# HIVE_SIGHT_DECAWAVE_B.net
KiCad netlist of a schematic drawn in Altium Designer
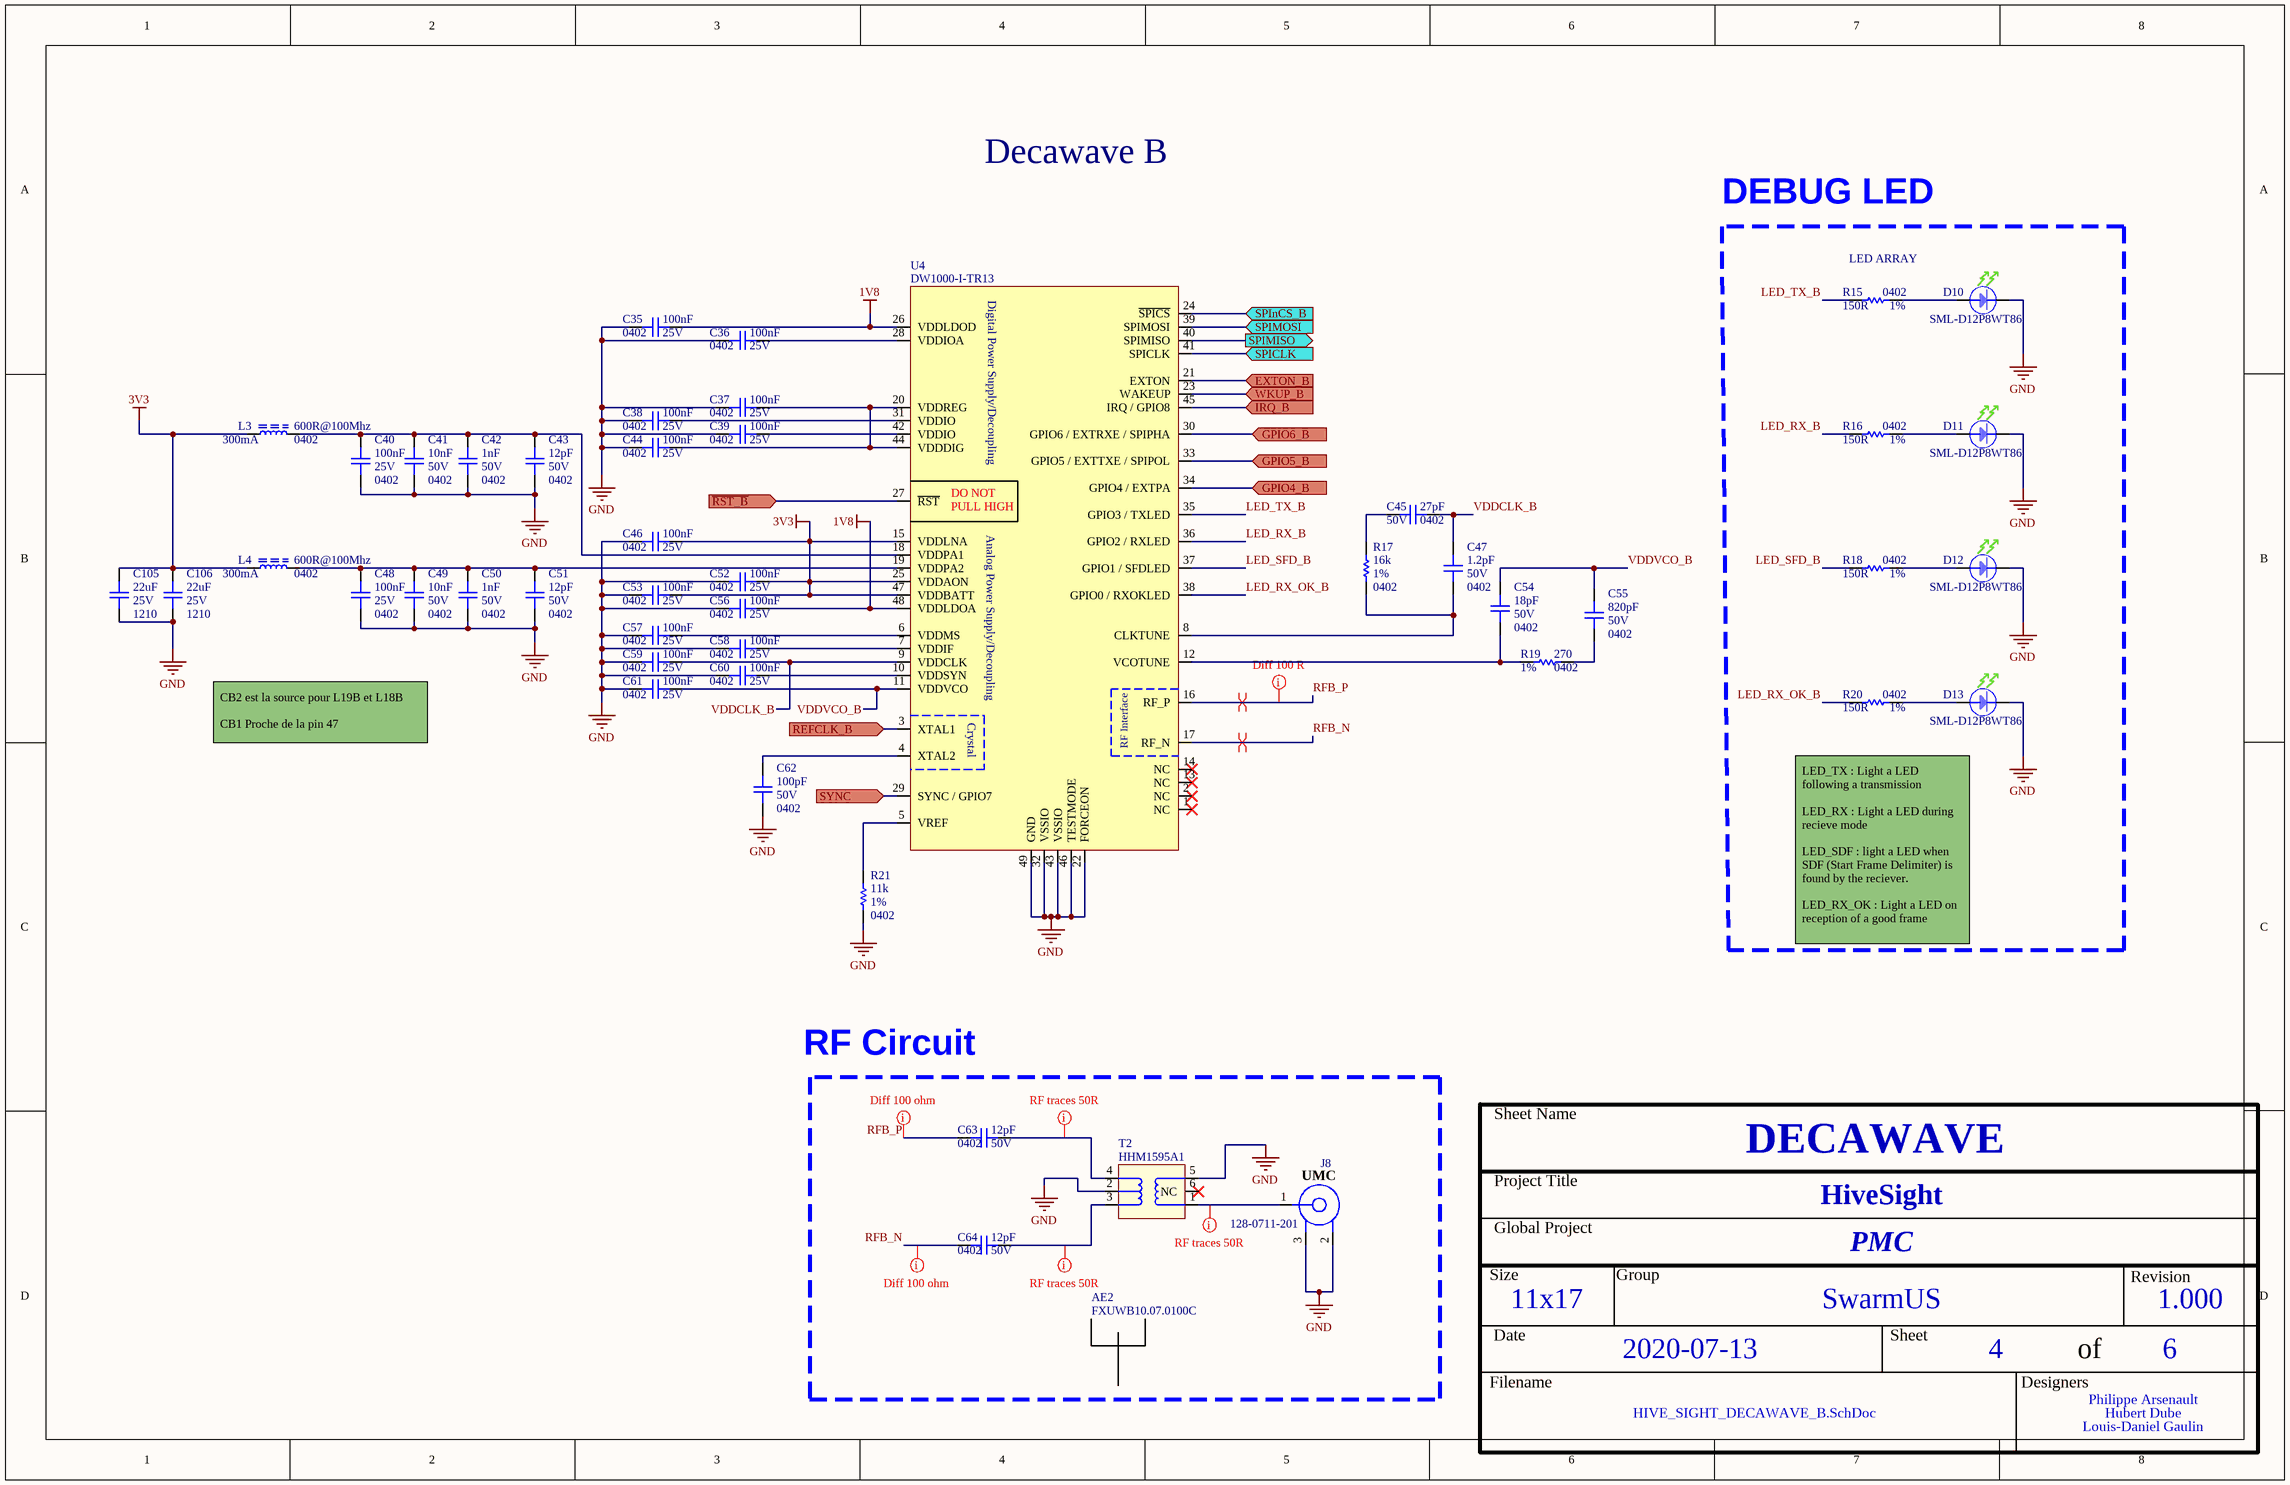
[diagram p0: HIVE_SIGHT_DECAWAVE_B.SchDoc]

(export (version "E")
  (design (tool "Eeschema 10.0.6"))
  (components
    (comp (ref "AE2")
      (value "FXUWB10.07.0100C")
      (description "External antenna - UWB - UMCC plug")
      (fields (field (name "CREATEDBY/DATE") "Philippe Arsenault"))
      (libsource (lib "SWARMUS_LIB") (part "ANT_FXUWB10.07.0100C"))
    )
    (comp (ref "C35")
      (value "100nF")
      (footprint "GRAMS_MASTER_LIB_PCB:CAP_CER_0402")
      (description "CAP - CER 0.1µF 10% 25V X7R - 0402")
      (fields
        (field (name "TOLERANCE") "10%")
        (field (name "PACKAGE") "0402")
        (field (name "VOLTAGE RATING") "25V")
        (field (name "Comment") "CGA2B3X7R1E104K050BB")
        (field (name "CREATEDBY/DATE") "Nicolas Roy 2018-11-07")
        (field (name "VERIFIEDBY") "Nicolas V. (2019-01-22)")
      )
      (libsource (lib "GRAMS_MASTER_LIB_SCH") (part "CAP_CER_CGA2B3X7R1E104K050BB"))
    )
    (comp (ref "C36")
      (value "100nF")
      (footprint "GRAMS_MASTER_LIB_PCB:CAP_CER_0402")
      (description "CAP - CER 0.1µF 10% 25V X7R - 0402")
      (fields
        (field (name "TOLERANCE") "10%")
        (field (name "PACKAGE") "0402")
        (field (name "VOLTAGE RATING") "25V")
        (field (name "Comment") "CGA2B3X7R1E104K050BB")
        (field (name "CREATEDBY/DATE") "Nicolas Roy 2018-11-07")
        (field (name "VERIFIEDBY") "Nicolas V. (2019-01-22)")
      )
      (libsource (lib "GRAMS_MASTER_LIB_SCH") (part "CAP_CER_CGA2B3X7R1E104K050BB"))
    )
    (comp (ref "C37")
      (value "100nF")
      (footprint "GRAMS_MASTER_LIB_PCB:CAP_CER_0402")
      (description "CAP - CER 0.1µF 10% 25V X7R - 0402")
      (fields
        (field (name "TOLERANCE") "10%")
        (field (name "PACKAGE") "0402")
        (field (name "VOLTAGE RATING") "25V")
        (field (name "Comment") "CGA2B3X7R1E104K050BB")
        (field (name "CREATEDBY/DATE") "Nicolas Roy 2018-11-07")
        (field (name "VERIFIEDBY") "Nicolas V. (2019-01-22)")
      )
      (libsource (lib "GRAMS_MASTER_LIB_SCH") (part "CAP_CER_CGA2B3X7R1E104K050BB"))
    )
    (comp (ref "C38")
      (value "100nF")
      (footprint "GRAMS_MASTER_LIB_PCB:CAP_CER_0402")
      (description "CAP - CER 0.1µF 10% 25V X7R - 0402")
      (fields
        (field (name "TOLERANCE") "10%")
        (field (name "PACKAGE") "0402")
        (field (name "VOLTAGE RATING") "25V")
        (field (name "Comment") "CGA2B3X7R1E104K050BB")
        (field (name "CREATEDBY/DATE") "Nicolas Roy 2018-11-07")
        (field (name "VERIFIEDBY") "Nicolas V. (2019-01-22)")
      )
      (libsource (lib "GRAMS_MASTER_LIB_SCH") (part "CAP_CER_CGA2B3X7R1E104K050BB"))
    )
    (comp (ref "C39")
      (value "100nF")
      (footprint "GRAMS_MASTER_LIB_PCB:CAP_CER_0402")
      (description "CAP - CER 0.1µF 10% 25V X7R - 0402")
      (fields
        (field (name "TOLERANCE") "10%")
        (field (name "PACKAGE") "0402")
        (field (name "VOLTAGE RATING") "25V")
        (field (name "Comment") "CGA2B3X7R1E104K050BB")
        (field (name "CREATEDBY/DATE") "Nicolas Roy 2018-11-07")
        (field (name "VERIFIEDBY") "Nicolas V. (2019-01-22)")
      )
      (libsource (lib "GRAMS_MASTER_LIB_SCH") (part "CAP_CER_CGA2B3X7R1E104K050BB"))
    )
    (comp (ref "C40")
      (value "100nF")
      (footprint "GRAMS_MASTER_LIB_PCB:CAP_CER_0402")
      (description "CAP - CER 0.1µF 10% 25V X7R - 0402")
      (fields
        (field (name "TOLERANCE") "10%")
        (field (name "PACKAGE") "0402")
        (field (name "VOLTAGE RATING") "25V")
        (field (name "Comment") "CGA2B3X7R1E104K050BB")
        (field (name "CREATEDBY/DATE") "Nicolas Roy 2018-11-07")
        (field (name "VERIFIEDBY") "Nicolas V. (2019-01-22)")
      )
      (libsource (lib "GRAMS_MASTER_LIB_SCH") (part "CAP_CER_CGA2B3X7R1E104K050BB"))
    )
    (comp (ref "C41")
      (value "10nF")
      (footprint "GRAMS_MASTER_LIB_PCB:CAP_CER_0402")
      (description "CAP - CER 10nF ±10% 50V X7R - 0402")
      (fields
        (field (name "TOLERANCE") "10%")
        (field (name "PACKAGE") "0402")
        (field (name "VOLTAGE RATING") "50V")
        (field (name "Comment") "CL05B103KB5NFNC")
        (field (name "CREATEDBY/DATE") "Keven Deslandes - 2018/11/20")
        (field (name "VERIFIEDBY") "Nicolas Roy - 2018/12/11")
      )
      (libsource (lib "GRAMS_MASTER_LIB_SCH") (part "CAP_CER_CL05B103KB5NFNC"))
    )
    (comp (ref "C42")
      (value "1nF")
      (footprint "CAP_CER_0402")
      (description "CAP - CER 1nF 10% 50V X7R - 0402")
      (fields
        (field (name "TOLERANCE") "10%")
        (field (name "PACKAGE") "0402")
        (field (name "VOLTAGE RATING") "50V")
        (field (name "Comment") "CC0402KRX7R9BB102")
        (field (name "CREATEDBY/DATE") "Jonathan Bouchard 2019-04-06")
        (field (name "VERIFIEDBY") "Nicolas V. (2019-04-30)")
      )
      (libsource (lib "GRAMS_MASTER_LIB_SCH") (part "CAP_CER_CC0402KRX7R9BB102"))
    )
    (comp (ref "C43")
      (value "12pF")
      (footprint "SWARMUS_LIB:CAP_CER_0402")
      (description "CAP - CER 12pF 50V ±5% C0G, NP0 - 0402")
      (fields
        (field (name "TOLERANCE") "±5%")
        (field (name "PACKAGE") "0402")
        (field (name "VOLTAGE RATING") "50V")
        (field (name "Comment") "CC0402JRNPO9BN120")
        (field (name "CREATEDBY/DATE") "Philippe Arsenault/ 2020-07-24")
        (field (name "VERIFIEDBY") "Louis-Daniel Gaulin / 2020-07-29")
      )
      (libsource (lib "SWARMUS_LIB") (part "CAP_CER_CC0402JRNPO9BN120"))
    )
    (comp (ref "C44")
      (value "100nF")
      (footprint "GRAMS_MASTER_LIB_PCB:CAP_CER_0402")
      (description "CAP - CER 0.1µF 10% 25V X7R - 0402")
      (fields
        (field (name "TOLERANCE") "10%")
        (field (name "PACKAGE") "0402")
        (field (name "VOLTAGE RATING") "25V")
        (field (name "Comment") "CGA2B3X7R1E104K050BB")
        (field (name "CREATEDBY/DATE") "Nicolas Roy 2018-11-07")
        (field (name "VERIFIEDBY") "Nicolas V. (2019-01-22)")
      )
      (libsource (lib "GRAMS_MASTER_LIB_SCH") (part "CAP_CER_CGA2B3X7R1E104K050BB"))
    )
    (comp (ref "C45")
      (value "27pF")
      (footprint "SWARMUS_LIB:CAP_CER_0402")
      (description "CAP - CER 27pF 50V ±5% C0G, NP0 - 0402")
      (fields
        (field (name "TOLERANCE") "±5%")
        (field (name "PACKAGE") "0402")
        (field (name "VOLTAGE RATING") "50V")
        (field (name "Comment") "CC0402JRNPO9BN270")
        (field (name "CREATEDBY/DATE") "Philippe Arsenault/ 2020-07-24")
        (field (name "VERIFIEDBY") "Louis-Daniel Gaulin / 2020-07-29")
      )
      (libsource (lib "SWARMUS_LIB") (part "CAP_CER_CC0402JRNPO9BN270"))
    )
    (comp (ref "C46")
      (value "100nF")
      (footprint "GRAMS_MASTER_LIB_PCB:CAP_CER_0402")
      (description "CAP - CER 0.1µF 10% 25V X7R - 0402")
      (fields
        (field (name "TOLERANCE") "10%")
        (field (name "PACKAGE") "0402")
        (field (name "VOLTAGE RATING") "25V")
        (field (name "Comment") "CGA2B3X7R1E104K050BB")
        (field (name "CREATEDBY/DATE") "Nicolas Roy 2018-11-07")
        (field (name "VERIFIEDBY") "Nicolas V. (2019-01-22)")
      )
      (libsource (lib "GRAMS_MASTER_LIB_SCH") (part "CAP_CER_CGA2B3X7R1E104K050BB"))
    )
    (comp (ref "C47")
      (value "1.2pF")
      (footprint "SWARMUS_LIB:CAP_CER_0402")
      (description "CAP - CER 1.2pF 50V ±0.25pF C0G, NP0 - 0402")
      (fields
        (field (name "TOLERANCE") "±0.25pF")
        (field (name "PACKAGE") "0402")
        (field (name "VOLTAGE RATING") "50V")
        (field (name "Comment") "C0402C129C5GACTU")
        (field (name "CREATEDBY/DATE") "Philippe Arsenault/ 2020-07-24")
        (field (name "VERIFIEDBY") "Louis-Daniel Gaulin / 2020-07-29")
      )
      (libsource (lib "SWARMUS_LIB") (part "CAP_CER_C0402C129C5GACTU"))
    )
    (comp (ref "C48")
      (value "100nF")
      (footprint "GRAMS_MASTER_LIB_PCB:CAP_CER_0402")
      (description "CAP - CER 0.1µF 10% 25V X7R - 0402")
      (fields
        (field (name "TOLERANCE") "10%")
        (field (name "PACKAGE") "0402")
        (field (name "VOLTAGE RATING") "25V")
        (field (name "Comment") "CGA2B3X7R1E104K050BB")
        (field (name "CREATEDBY/DATE") "Nicolas Roy 2018-11-07")
        (field (name "VERIFIEDBY") "Nicolas V. (2019-01-22)")
      )
      (libsource (lib "GRAMS_MASTER_LIB_SCH") (part "CAP_CER_CGA2B3X7R1E104K050BB"))
    )
    (comp (ref "C49")
      (value "10nF")
      (footprint "GRAMS_MASTER_LIB_PCB:CAP_CER_0402")
      (description "CAP - CER 10nF ±10% 50V X7R - 0402")
      (fields
        (field (name "TOLERANCE") "10%")
        (field (name "PACKAGE") "0402")
        (field (name "VOLTAGE RATING") "50V")
        (field (name "Comment") "CL05B103KB5NFNC")
        (field (name "CREATEDBY/DATE") "Keven Deslandes - 2018/11/20")
        (field (name "VERIFIEDBY") "Nicolas Roy - 2018/12/11")
      )
      (libsource (lib "GRAMS_MASTER_LIB_SCH") (part "CAP_CER_CL05B103KB5NFNC"))
    )
    (comp (ref "C50")
      (value "1nF")
      (footprint "CAP_CER_0402")
      (description "CAP - CER 1nF 10% 50V X7R - 0402")
      (fields
        (field (name "TOLERANCE") "10%")
        (field (name "PACKAGE") "0402")
        (field (name "VOLTAGE RATING") "50V")
        (field (name "Comment") "CC0402KRX7R9BB102")
        (field (name "CREATEDBY/DATE") "Jonathan Bouchard 2019-04-06")
        (field (name "VERIFIEDBY") "Nicolas V. (2019-04-30)")
      )
      (libsource (lib "GRAMS_MASTER_LIB_SCH") (part "CAP_CER_CC0402KRX7R9BB102"))
    )
    (comp (ref "C51")
      (value "12pF")
      (footprint "SWARMUS_LIB:CAP_CER_0402")
      (description "CAP - CER 12pF 50V ±5% C0G, NP0 - 0402")
      (fields
        (field (name "TOLERANCE") "±5%")
        (field (name "PACKAGE") "0402")
        (field (name "VOLTAGE RATING") "50V")
        (field (name "Comment") "CC0402JRNPO9BN120")
        (field (name "CREATEDBY/DATE") "Philippe Arsenault/ 2020-07-24")
        (field (name "VERIFIEDBY") "Louis-Daniel Gaulin / 2020-07-29")
      )
      (libsource (lib "SWARMUS_LIB") (part "CAP_CER_CC0402JRNPO9BN120"))
    )
    (comp (ref "C52")
      (value "100nF")
      (footprint "GRAMS_MASTER_LIB_PCB:CAP_CER_0402")
      (description "CAP - CER 0.1µF 10% 25V X7R - 0402")
      (fields
        (field (name "TOLERANCE") "10%")
        (field (name "PACKAGE") "0402")
        (field (name "VOLTAGE RATING") "25V")
        (field (name "Comment") "CGA2B3X7R1E104K050BB")
        (field (name "CREATEDBY/DATE") "Nicolas Roy 2018-11-07")
        (field (name "VERIFIEDBY") "Nicolas V. (2019-01-22)")
      )
      (libsource (lib "GRAMS_MASTER_LIB_SCH") (part "CAP_CER_CGA2B3X7R1E104K050BB"))
    )
    (comp (ref "C53")
      (value "100nF")
      (footprint "GRAMS_MASTER_LIB_PCB:CAP_CER_0402")
      (description "CAP - CER 0.1µF 10% 25V X7R - 0402")
      (fields
        (field (name "TOLERANCE") "10%")
        (field (name "PACKAGE") "0402")
        (field (name "VOLTAGE RATING") "25V")
        (field (name "Comment") "CGA2B3X7R1E104K050BB")
        (field (name "CREATEDBY/DATE") "Nicolas Roy 2018-11-07")
        (field (name "VERIFIEDBY") "Nicolas V. (2019-01-22)")
      )
      (libsource (lib "GRAMS_MASTER_LIB_SCH") (part "CAP_CER_CGA2B3X7R1E104K050BB"))
    )
    (comp (ref "C54")
      (value "18pF")
      (footprint "CAP_CER_0402")
      (description "CAP - CER 18pF 50V C0G, NPO - 0402")
      (fields
        (field (name "TOLERANCE") "2%")
        (field (name "PACKAGE") "0402")
        (field (name "VOLTAGE RATING") "50V")
        (field (name "Comment") "GRM1555C1H180GA01D")
        (field (name "CREATEDBY/DATE") "Tommy Rossignol / 2018-11-20")
        (field (name "VERIFIEDBY") "Caroline Paulin - 13 fév 2019")
      )
      (libsource (lib "GRAMS_MASTER_LIB_SCH") (part "CAP_CER_GRM1555C1H180GA01D"))
    )
    (comp (ref "C55")
      (value "820pF")
      (footprint "SWARMUS_LIB:CAP_CER_0402")
      (description "CAP - CER 820pF 50V ±10% X7R - 0402")
      (fields
        (field (name "TOLERANCE") "±10%")
        (field (name "PACKAGE") "0402")
        (field (name "VOLTAGE RATING") "50V")
        (field (name "Comment") "CC0402KRX7R9BB821")
        (field (name "CREATEDBY/DATE") "Philippe Arsenault/ 2020-07-24")
        (field (name "VERIFIEDBY") "Louis-Daniel Gaulin / 2020-07-29")
      )
      (libsource (lib "SWARMUS_LIB") (part "CAP_CER_CC0402KRX7R9BB821"))
    )
    (comp (ref "C56")
      (value "100nF")
      (footprint "GRAMS_MASTER_LIB_PCB:CAP_CER_0402")
      (description "CAP - CER 0.1µF 10% 25V X7R - 0402")
      (fields
        (field (name "TOLERANCE") "10%")
        (field (name "PACKAGE") "0402")
        (field (name "VOLTAGE RATING") "25V")
        (field (name "Comment") "CGA2B3X7R1E104K050BB")
        (field (name "CREATEDBY/DATE") "Nicolas Roy 2018-11-07")
        (field (name "VERIFIEDBY") "Nicolas V. (2019-01-22)")
      )
      (libsource (lib "GRAMS_MASTER_LIB_SCH") (part "CAP_CER_CGA2B3X7R1E104K050BB"))
    )
    (comp (ref "C57")
      (value "100nF")
      (footprint "GRAMS_MASTER_LIB_PCB:CAP_CER_0402")
      (description "CAP - CER 0.1µF 10% 25V X7R - 0402")
      (fields
        (field (name "TOLERANCE") "10%")
        (field (name "PACKAGE") "0402")
        (field (name "VOLTAGE RATING") "25V")
        (field (name "Comment") "CGA2B3X7R1E104K050BB")
        (field (name "CREATEDBY/DATE") "Nicolas Roy 2018-11-07")
        (field (name "VERIFIEDBY") "Nicolas V. (2019-01-22)")
      )
      (libsource (lib "GRAMS_MASTER_LIB_SCH") (part "CAP_CER_CGA2B3X7R1E104K050BB"))
    )
    (comp (ref "C58")
      (value "100nF")
      (footprint "GRAMS_MASTER_LIB_PCB:CAP_CER_0402")
      (description "CAP - CER 0.1µF 10% 25V X7R - 0402")
      (fields
        (field (name "TOLERANCE") "10%")
        (field (name "PACKAGE") "0402")
        (field (name "VOLTAGE RATING") "25V")
        (field (name "Comment") "CGA2B3X7R1E104K050BB")
        (field (name "CREATEDBY/DATE") "Nicolas Roy 2018-11-07")
        (field (name "VERIFIEDBY") "Nicolas V. (2019-01-22)")
      )
      (libsource (lib "GRAMS_MASTER_LIB_SCH") (part "CAP_CER_CGA2B3X7R1E104K050BB"))
    )
    (comp (ref "C59")
      (value "100nF")
      (footprint "GRAMS_MASTER_LIB_PCB:CAP_CER_0402")
      (description "CAP - CER 0.1µF 10% 25V X7R - 0402")
      (fields
        (field (name "TOLERANCE") "10%")
        (field (name "PACKAGE") "0402")
        (field (name "VOLTAGE RATING") "25V")
        (field (name "Comment") "CGA2B3X7R1E104K050BB")
        (field (name "CREATEDBY/DATE") "Nicolas Roy 2018-11-07")
        (field (name "VERIFIEDBY") "Nicolas V. (2019-01-22)")
      )
      (libsource (lib "GRAMS_MASTER_LIB_SCH") (part "CAP_CER_CGA2B3X7R1E104K050BB"))
    )
    (comp (ref "C60")
      (value "100nF")
      (footprint "GRAMS_MASTER_LIB_PCB:CAP_CER_0402")
      (description "CAP - CER 0.1µF 10% 25V X7R - 0402")
      (fields
        (field (name "TOLERANCE") "10%")
        (field (name "PACKAGE") "0402")
        (field (name "VOLTAGE RATING") "25V")
        (field (name "Comment") "CGA2B3X7R1E104K050BB")
        (field (name "CREATEDBY/DATE") "Nicolas Roy 2018-11-07")
        (field (name "VERIFIEDBY") "Nicolas V. (2019-01-22)")
      )
      (libsource (lib "GRAMS_MASTER_LIB_SCH") (part "CAP_CER_CGA2B3X7R1E104K050BB"))
    )
    (comp (ref "C61")
      (value "100nF")
      (footprint "GRAMS_MASTER_LIB_PCB:CAP_CER_0402")
      (description "CAP - CER 0.1µF 10% 25V X7R - 0402")
      (fields
        (field (name "TOLERANCE") "10%")
        (field (name "PACKAGE") "0402")
        (field (name "VOLTAGE RATING") "25V")
        (field (name "Comment") "CGA2B3X7R1E104K050BB")
        (field (name "CREATEDBY/DATE") "Nicolas Roy 2018-11-07")
        (field (name "VERIFIEDBY") "Nicolas V. (2019-01-22)")
      )
      (libsource (lib "GRAMS_MASTER_LIB_SCH") (part "CAP_CER_CGA2B3X7R1E104K050BB"))
    )
    (comp (ref "C62")
      (value "100pF")
      (footprint "SWARMUS_LIB:CAP_CER_0402")
      (description "CAP - CER 100pF 50V ±5% C0G,CP0 - 0402")
      (fields
        (field (name "TOLERANCE") "±5%")
        (field (name "PACKAGE") "0402")
        (field (name "VOLTAGE RATING") "50V")
        (field (name "Comment") "CC0402JRNPO9BN101")
        (field (name "CREATEDBY/DATE") "Philippe Arsenault/ 2020-07-24")
        (field (name "VERIFIEDBY") "Louis-Daniel Gaulin / 2020-07-29")
      )
      (libsource (lib "SWARMUS_LIB") (part "CAP_CER_CC0402JRNPO9BN101"))
    )
    (comp (ref "C63")
      (value "12pF")
      (footprint "SWARMUS_LIB:CAP_CER_0402")
      (description "CAP - CER 12pF 50V ±5% C0G, NP0 - 0402")
      (fields
        (field (name "TOLERANCE") "±5%")
        (field (name "PACKAGE") "0402")
        (field (name "VOLTAGE RATING") "50V")
        (field (name "Comment") "CC0402JRNPO9BN120")
        (field (name "CREATEDBY/DATE") "Philippe Arsenault/ 2020-07-24")
        (field (name "VERIFIEDBY") "Louis-Daniel Gaulin / 2020-07-29")
      )
      (libsource (lib "SWARMUS_LIB") (part "CAP_CER_CC0402JRNPO9BN120"))
    )
    (comp (ref "C64")
      (value "12pF")
      (footprint "SWARMUS_LIB:CAP_CER_0402")
      (description "CAP - CER 12pF 50V ±5% C0G, NP0 - 0402")
      (fields
        (field (name "TOLERANCE") "±5%")
        (field (name "PACKAGE") "0402")
        (field (name "VOLTAGE RATING") "50V")
        (field (name "Comment") "CC0402JRNPO9BN120")
        (field (name "CREATEDBY/DATE") "Philippe Arsenault/ 2020-07-24")
        (field (name "VERIFIEDBY") "Louis-Daniel Gaulin / 2020-07-29")
      )
      (libsource (lib "SWARMUS_LIB") (part "CAP_CER_CC0402JRNPO9BN120"))
    )
    (comp (ref "C105")
      (value "22uF")
      (footprint "GRAMS_MASTER_LIB_PCB:CAP_CER_1210")
      (description "CAP - CER 22UF 20% 25V X7R - 1210")
      (fields
        (field (name "TOLERANCE") "20%")
        (field (name "PACKAGE") "1210")
        (field (name "VOLTAGE RATING") "25V")
        (field (name "Comment") "C3225X7R1E226M250AB")
        (field (name "CREATEDBY/DATE") "Nicolas V. (2019-12-11)")
        (field (name "VERIFIEDBY") "Nicolas V. (2019-12-11)")
      )
      (libsource (lib "GRAMS_MASTER_LIB_SCH") (part "CAP_CER_C3225X7R1E226M250AB"))
    )
    (comp (ref "C106")
      (value "22uF")
      (footprint "GRAMS_MASTER_LIB_PCB:CAP_CER_1210")
      (description "CAP - CER 22UF 20% 25V X7R - 1210")
      (fields
        (field (name "TOLERANCE") "20%")
        (field (name "PACKAGE") "1210")
        (field (name "VOLTAGE RATING") "25V")
        (field (name "Comment") "C3225X7R1E226M250AB")
        (field (name "CREATEDBY/DATE") "Nicolas V. (2019-12-11)")
        (field (name "VERIFIEDBY") "Nicolas V. (2019-12-11)")
      )
      (libsource (lib "GRAMS_MASTER_LIB_SCH") (part "CAP_CER_C3225X7R1E226M250AB"))
    )
    (comp (ref "D10")
      (value "SML-D12P8WT86")
      (footprint "GRAMS_MASTER_LIB_PCB:LED_SML-D12P8WT86")
      (description "LED - GREEN DIFFUSED 0603 SMD - 0603")
      (fields
        (field (name "CREATEDBY/DATE") "Keven Deslandes - 2018/11/21")
        (field (name "VERIFIEDBY") "Caroline Paulin - 13 février 2019")
      )
      (libsource (lib "GRAMS_MASTER_LIB_SCH") (part "LED_SML-D12P8WT86"))
    )
    (comp (ref "D11")
      (value "SML-D12P8WT86")
      (footprint "GRAMS_MASTER_LIB_PCB:LED_SML-D12P8WT86")
      (description "LED - GREEN DIFFUSED 0603 SMD - 0603")
      (fields
        (field (name "CREATEDBY/DATE") "Keven Deslandes - 2018/11/21")
        (field (name "VERIFIEDBY") "Caroline Paulin - 13 février 2019")
      )
      (libsource (lib "GRAMS_MASTER_LIB_SCH") (part "LED_SML-D12P8WT86"))
    )
    (comp (ref "D12")
      (value "SML-D12P8WT86")
      (footprint "GRAMS_MASTER_LIB_PCB:LED_SML-D12P8WT86")
      (description "LED - GREEN DIFFUSED 0603 SMD - 0603")
      (fields
        (field (name "CREATEDBY/DATE") "Keven Deslandes - 2018/11/21")
        (field (name "VERIFIEDBY") "Caroline Paulin - 13 février 2019")
      )
      (libsource (lib "GRAMS_MASTER_LIB_SCH") (part "LED_SML-D12P8WT86"))
    )
    (comp (ref "D13")
      (value "SML-D12P8WT86")
      (footprint "GRAMS_MASTER_LIB_PCB:LED_SML-D12P8WT86")
      (description "LED - GREEN DIFFUSED 0603 SMD - 0603")
      (fields
        (field (name "CREATEDBY/DATE") "Keven Deslandes - 2018/11/21")
        (field (name "VERIFIEDBY") "Caroline Paulin - 13 février 2019")
      )
      (libsource (lib "GRAMS_MASTER_LIB_SCH") (part "LED_SML-D12P8WT86"))
    )
    (comp (ref "J8")
      (value "128-0711-201")
      (footprint "GRAMS_MASTER_LIB_PCB:CON_UMC_128-0711-201")
      (description "CON - UMC JACK STR 50 OHM - SMD")
      (fields
        (field (name "CREATEDBY/DATE") "Keven Desandes - 2018/09/27")
        (field (name "VERIFIEDBY") "Caroline Paulin - 23 janv 2019")
      )
      (libsource (lib "GRAMS_MASTER_LIB_SCH") (part "CON_UMC_128-0711-201"))
    )
    (comp (ref "L3")
      (value "600R@100Mhz")
      (footprint "GRAMS_MASTER_LIB_PCB:FER_0603")
      (description "FER - FERRITE BEAD 600 OHM@100MHz - 0402")
      (fields
        (field (name "CURRENT RATING") "300mA")
        (field (name "PACKAGE") "0402")
        (field (name "Comment") "BLM15AG601SN1D")
        (field (name "CREATEDBY/DATE") "Philippe Arsenault/2020-07-24")
      )
      (libsource (lib "a_Valider_PA") (part "FER_BLM15AG601SN1D"))
    )
    (comp (ref "L4")
      (value "600R@100Mhz")
      (footprint "GRAMS_MASTER_LIB_PCB:FER_0603")
      (description "FER - FERRITE BEAD 600 OHM@100MHz - 0402")
      (fields
        (field (name "CURRENT RATING") "300mA")
        (field (name "PACKAGE") "0402")
        (field (name "Comment") "BLM15AG601SN1D")
        (field (name "CREATEDBY/DATE") "Philippe Arsenault/2020-07-24")
      )
      (libsource (lib "a_Valider_PA") (part "FER_BLM15AG601SN1D"))
    )
    (comp (ref "R15")
      (value "150R")
      (footprint "RES_0402")
      (description "RES - 150R 1% 1/16W - 0402")
      (fields
        (field (name "TOLERANCE") "1%")
        (field (name "PACKAGE") "0402")
        (field (name "Comment") "RC0402FR-07150RL")
        (field (name "CREATEDBY/DATE") "Jonathan Bouchard 2019-03-25")
        (field (name "VERIFIEDBY") "Nicolas V. (2019-05-02)")
      )
      (libsource (lib "GRAMS_MASTER_LIB_SCH") (part "RES_RC0402FR-07150RL"))
    )
    (comp (ref "R16")
      (value "150R")
      (footprint "RES_0402")
      (description "RES - 150R 1% 1/16W - 0402")
      (fields
        (field (name "TOLERANCE") "1%")
        (field (name "PACKAGE") "0402")
        (field (name "Comment") "RC0402FR-07150RL")
        (field (name "CREATEDBY/DATE") "Jonathan Bouchard 2019-03-25")
        (field (name "VERIFIEDBY") "Nicolas V. (2019-05-02)")
      )
      (libsource (lib "GRAMS_MASTER_LIB_SCH") (part "RES_RC0402FR-07150RL"))
    )
    (comp (ref "R17")
      (value "16k")
      (footprint "GRAMS_MASTER_LIB_PCB:RES_0402")
      (description "RES - 16k OHM 1% 1/16W - 0402")
      (fields
        (field (name "TOLERANCE") "1%")
        (field (name "PACKAGE") "0402")
        (field (name "Comment") "RC0402FR-0716KL")
        (field (name "CREATEDBY/DATE") "Nicolas Roy/18 oct. 2018")
        (field (name "VERIFIEDBY") "Caroline Paulin - 18/12/2018")
      )
      (libsource (lib "GRAMS_MASTER_LIB_SCH") (part "RES_RC0402FR-0716KL"))
    )
    (comp (ref "R18")
      (value "150R")
      (footprint "RES_0402")
      (description "RES - 150R 1% 1/16W - 0402")
      (fields
        (field (name "TOLERANCE") "1%")
        (field (name "PACKAGE") "0402")
        (field (name "Comment") "RC0402FR-07150RL")
        (field (name "CREATEDBY/DATE") "Jonathan Bouchard 2019-03-25")
        (field (name "VERIFIEDBY") "Nicolas V. (2019-05-02)")
      )
      (libsource (lib "GRAMS_MASTER_LIB_SCH") (part "RES_RC0402FR-07150RL"))
    )
    (comp (ref "R19")
      (value "270")
      (footprint "FER_0402")
      (description "RES - 270R 1% 1/16W - 0402")
      (fields
        (field (name "TOLERANCE") "1%")
        (field (name "PACKAGE") "0402")
        (field (name "Comment") "RC0402FR-07270RL")
        (field (name "CREATEDBY/DATE") "Philippe Arsenault 2020-07-24")
        (field (name "VERIFIEDBY") "Louis-Daniel Gaulin / 03-10-2020")
      )
      (libsource (lib "SWARMUS_LIB") (part "RES_RC0402FR-07270RL"))
    )
    (comp (ref "R20")
      (value "150R")
      (footprint "RES_0402")
      (description "RES - 150R 1% 1/16W - 0402")
      (fields
        (field (name "TOLERANCE") "1%")
        (field (name "PACKAGE") "0402")
        (field (name "Comment") "RC0402FR-07150RL")
        (field (name "CREATEDBY/DATE") "Jonathan Bouchard 2019-03-25")
        (field (name "VERIFIEDBY") "Nicolas V. (2019-05-02)")
      )
      (libsource (lib "GRAMS_MASTER_LIB_SCH") (part "RES_RC0402FR-07150RL"))
    )
    (comp (ref "R21")
      (value "11k")
      (footprint "GRAMS_MASTER_LIB_PCB:RES_0402")
      (description "RES - 11K 1% 1/16W - 0402")
      (fields
        (field (name "TOLERANCE") "1%")
        (field (name "PACKAGE") "0402")
        (field (name "Comment") "RC0402FR-0711KL")
        (field (name "CREATEDBY/DATE") "Keven Deslandes 2018-10-15")
        (field (name "VERIFIEDBY") "Carolilne Paulin - 18/12/2018")
      )
      (libsource (lib "GRAMS_MASTER_LIB_SCH") (part "RES_RC0402FR-0711KL"))
    )
    (comp (ref "T2")
      (value "HHM1595A1")
      (footprint "XFR_HHM1595A1")
      (description "XFR - Imp Unbalaced/Balanced 50/100 3-8GHz  -SMD")
      (fields
        (field (name "CREATEDBY/DATE") "Philippe Arsenault/2020-21-07")
        (field (name "VERIFIEDBY") "Louis-Daniel Gaulin / 03-10-2020")
      )
      (libsource (lib "SWARMUS_LIB") (part "XFR_HHM1595A1"))
    )
    (comp (ref "U4")
      (value "DW1000-I-TR13")
      (footprint "SWARMUS_LIB:COM_XCV_DW1000-I-TR13")
      (description "COM - IC RF TxRx 802.15.4 IR-UWB DECAWAVE - 48-VFQFN EP")
      (fields (field (name "CREATEDBY/DATE") "Philippe Arsenault/13-07-2020"))
      (libsource (lib "SWARMUS_LIB") (part "COM_XCV_DW1000-I-TR13"))
    )
  )
  (nets
    (net (code "1") (name "/EXTON_B") (class "Default")
      (node (ref "U4") (pin "21") (pinfunction "EXTON_21") (pintype "passive"))
    )
    (net (code "2") (name "/GPIO4_B") (class "Default")
      (node (ref "U4") (pin "34") (pinfunction "GPIO4_/_EXTPA_34") (pintype "passive"))
    )
    (net (code "3") (name "/GPIO5_B") (class "Default")
      (node (ref "U4") (pin "33") (pinfunction "GPIO5_/_EXTTXE_/_SPIPOL_33") (pintype "passive"))
    )
    (net (code "4") (name "/GPIO6_B") (class "Default")
      (node (ref "U4") (pin "30") (pinfunction "GPIO6_/_EXTRXE_/_SPIPHA_30") (pintype "passive"))
    )
    (net (code "5") (name "/IRQ_B") (class "Default")
      (node (ref "U4") (pin "45") (pinfunction "IRQ_/_GPIO8_45") (pintype "passive"))
    )
    (net (code "6") (name "/LED_RX_B") (class "Default")
      (node (ref "R16") (pin "2") (pinfunction "2_2") (pintype "passive"))
      (node (ref "U4") (pin "36") (pinfunction "GPIO2_/_RXLED_36") (pintype "passive"))
    )
    (net (code "7") (name "/LED_RX_OK_B") (class "Default")
      (node (ref "R20") (pin "2") (pinfunction "2_2") (pintype "passive"))
      (node (ref "U4") (pin "38") (pinfunction "GPIO0_/_RXOKLED_38") (pintype "passive"))
    )
    (net (code "8") (name "/LED_SFD_B") (class "Default")
      (node (ref "R18") (pin "2") (pinfunction "2_2") (pintype "passive"))
      (node (ref "U4") (pin "37") (pinfunction "GPIO1_/_SFDLED_37") (pintype "passive"))
    )
    (net (code "9") (name "/LED_TX_B") (class "Default")
      (node (ref "R15") (pin "2") (pinfunction "2_2") (pintype "passive"))
      (node (ref "U4") (pin "35") (pinfunction "GPIO3_/_TXLED_35") (pintype "passive"))
    )
    (net (code "10") (name "/REFCLK_B") (class "Default")
      (node (ref "U4") (pin "3") (pinfunction "XTAL1_3") (pintype "passive"))
    )
    (net (code "11") (name "/RFB_N") (class "Default")
      (node (ref "C64") (pin "2") (pinfunction "2_2") (pintype "passive"))
      (node (ref "U4") (pin "17") (pinfunction "RF_N_17") (pintype "passive"))
    )
    (net (code "12") (name "/RFB_P") (class "Default")
      (node (ref "C63") (pin "2") (pinfunction "2_2") (pintype "passive"))
      (node (ref "U4") (pin "16") (pinfunction "RF_P_16") (pintype "passive"))
    )
    (net (code "13") (name "/RST_B") (class "Default")
      (node (ref "U4") (pin "27") (pinfunction "RST_27") (pintype "passive"))
    )
    (net (code "14") (name "/SPICLK") (class "Default")
      (node (ref "U4") (pin "41") (pinfunction "SPICLK_41") (pintype "passive"))
    )
    (net (code "15") (name "/SPIMISO") (class "Default")
      (node (ref "U4") (pin "40") (pinfunction "SPIMISO_40") (pintype "passive"))
    )
    (net (code "16") (name "/SPIMOSI") (class "Default")
      (node (ref "U4") (pin "39") (pinfunction "SPIMOSI_39") (pintype "passive"))
    )
    (net (code "17") (name "/SPInCS_B") (class "Default")
      (node (ref "U4") (pin "24") (pinfunction "SPICS_24") (pintype "passive"))
    )
    (net (code "18") (name "/SYNC") (class "Default")
      (node (ref "U4") (pin "29") (pinfunction "SYNC_/_GPIO7_29") (pintype "passive"))
    )
    (net (code "19") (name "/VDDCLK_B") (class "Default")
      (node (ref "C45") (pin "1") (pinfunction "1_1") (pintype "passive"))
      (node (ref "C47") (pin "2") (pinfunction "2_2") (pintype "passive"))
      (node (ref "C59") (pin "1") (pinfunction "1_1") (pintype "passive"))
      (node (ref "U4") (pin "9") (pinfunction "VDDCLK_9") (pintype "passive"))
    )
    (net (code "20") (name "/VDDVCO_B") (class "Default")
      (node (ref "C54") (pin "2") (pinfunction "2_2") (pintype "passive"))
      (node (ref "C55") (pin "2") (pinfunction "2_2") (pintype "passive"))
      (node (ref "C61") (pin "1") (pinfunction "1_1") (pintype "passive"))
      (node (ref "U4") (pin "11") (pinfunction "VDDVCO_11") (pintype "passive"))
    )
    (net (code "21") (name "/WKUP_B") (class "Default")
      (node (ref "U4") (pin "23") (pinfunction "WAKEUP_23") (pintype "passive"))
    )
    (net (code "22") (name "1V8") (class "Default")
      (node (ref "C35") (pin "1") (pinfunction "1_1") (pintype "passive"))
      (node (ref "C56") (pin "1") (pinfunction "1_1") (pintype "passive"))
      (node (ref "U4") (pin "26") (pinfunction "VDDLDOD_26") (pintype "passive"))
      (node (ref "U4") (pin "48") (pinfunction "VDDLDOA_48") (pintype "passive"))
    )
    (net (code "23") (name "3V3") (class "Default")
      (node (ref "C105") (pin "2") (pinfunction "2_2") (pintype "passive"))
      (node (ref "C106") (pin "2") (pinfunction "2_2") (pintype "passive"))
      (node (ref "C46") (pin "1") (pinfunction "1_1") (pintype "passive"))
      (node (ref "C52") (pin "1") (pinfunction "1_1") (pintype "passive"))
      (node (ref "C53") (pin "1") (pinfunction "1_1") (pintype "passive"))
      (node (ref "L3") (pin "1") (pinfunction "1_1") (pintype "passive"))
      (node (ref "L4") (pin "1") (pinfunction "1_1") (pintype "passive"))
      (node (ref "U4") (pin "15") (pinfunction "VDDLNA_15") (pintype "passive"))
      (node (ref "U4") (pin "25") (pinfunction "VDDAON_25") (pintype "passive"))
      (node (ref "U4") (pin "47") (pinfunction "VDDBATT_47") (pintype "passive"))
    )
    (net (code "24") (name "GND") (class "Default")
      (node (ref "C105") (pin "1") (pinfunction "1_1") (pintype "passive"))
      (node (ref "C106") (pin "1") (pinfunction "1_1") (pintype "passive"))
      (node (ref "C35") (pin "2") (pinfunction "2_2") (pintype "passive"))
      (node (ref "C36") (pin "2") (pinfunction "2_2") (pintype "passive"))
      (node (ref "C37") (pin "2") (pinfunction "2_2") (pintype "passive"))
      (node (ref "C38") (pin "2") (pinfunction "2_2") (pintype "passive"))
      (node (ref "C39") (pin "2") (pinfunction "2_2") (pintype "passive"))
      (node (ref "C40") (pin "1") (pinfunction "1_1") (pintype "passive"))
      (node (ref "C41") (pin "1") (pinfunction "1_1") (pintype "passive"))
      (node (ref "C42") (pin "1") (pinfunction "1_1") (pintype "passive"))
      (node (ref "C43") (pin "1") (pinfunction "1_1") (pintype "passive"))
      (node (ref "C44") (pin "2") (pinfunction "2_2") (pintype "passive"))
      (node (ref "C46") (pin "2") (pinfunction "2_2") (pintype "passive"))
      (node (ref "C48") (pin "1") (pinfunction "1_1") (pintype "passive"))
      (node (ref "C49") (pin "1") (pinfunction "1_1") (pintype "passive"))
      (node (ref "C50") (pin "1") (pinfunction "1_1") (pintype "passive"))
      (node (ref "C51") (pin "1") (pinfunction "1_1") (pintype "passive"))
      (node (ref "C52") (pin "2") (pinfunction "2_2") (pintype "passive"))
      (node (ref "C53") (pin "2") (pinfunction "2_2") (pintype "passive"))
      (node (ref "C56") (pin "2") (pinfunction "2_2") (pintype "passive"))
      (node (ref "C57") (pin "2") (pinfunction "2_2") (pintype "passive"))
      (node (ref "C58") (pin "2") (pinfunction "2_2") (pintype "passive"))
      (node (ref "C59") (pin "2") (pinfunction "2_2") (pintype "passive"))
      (node (ref "C60") (pin "2") (pinfunction "2_2") (pintype "passive"))
      (node (ref "C61") (pin "2") (pinfunction "2_2") (pintype "passive"))
      (node (ref "C62") (pin "1") (pinfunction "1_1") (pintype "passive"))
      (node (ref "D10") (pin "K") (pinfunction "K_K") (pintype "passive"))
      (node (ref "D11") (pin "K") (pinfunction "K_K") (pintype "passive"))
      (node (ref "D12") (pin "K") (pinfunction "K_K") (pintype "passive"))
      (node (ref "D13") (pin "K") (pinfunction "K_K") (pintype "passive"))
      (node (ref "J8") (pin "2") (pinfunction "2_2") (pintype "passive"))
      (node (ref "J8") (pin "3") (pinfunction "3_3") (pintype "passive"))
      (node (ref "R21") (pin "1") (pinfunction "1_1") (pintype "passive"))
      (node (ref "T2") (pin "2") (pinfunction "GND_2") (pintype "passive"))
      (node (ref "T2") (pin "5") (pinfunction "5_5") (pintype "passive"))
      (node (ref "U4") (pin "22") (pinfunction "FORCEON_22") (pintype "passive"))
      (node (ref "U4") (pin "32") (pinfunction "VSSIO_32") (pintype "passive"))
      (node (ref "U4") (pin "43") (pinfunction "VSSIO_43") (pintype "passive"))
      (node (ref "U4") (pin "46") (pinfunction "TESTMODE_46") (pintype "passive"))
      (node (ref "U4") (pin "49") (pinfunction "GND_49") (pintype "passive"))
    )
    (net (code "25") (name "Net-(C38-Pad1)") (class "Default")
      (node (ref "C38") (pin "1") (pinfunction "1_1") (pintype "passive"))
      (node (ref "U4") (pin "31") (pinfunction "VDDIO_31") (pintype "passive"))
    )
    (net (code "26") (name "Net-(C39-Pad1)") (class "Default")
      (node (ref "C39") (pin "1") (pinfunction "1_1") (pintype "passive"))
      (node (ref "U4") (pin "42") (pinfunction "VDDIO_42") (pintype "passive"))
    )
    (net (code "27") (name "Net-(C45-Pad2)") (class "Default")
      (node (ref "C45") (pin "2") (pinfunction "2_2") (pintype "passive"))
      (node (ref "R17") (pin "2") (pinfunction "2_2") (pintype "passive"))
    )
    (net (code "28") (name "Net-(C55-Pad1)") (class "Default")
      (node (ref "C55") (pin "1") (pinfunction "1_1") (pintype "passive"))
      (node (ref "R19") (pin "1") (pinfunction "1_1") (pintype "passive"))
    )
    (net (code "29") (name "Net-(C63-Pad1)") (class "Default")
      (node (ref "C63") (pin "1") (pinfunction "1_1") (pintype "passive"))
      (node (ref "T2") (pin "4") (pinfunction "4_4") (pintype "passive"))
    )
    (net (code "30") (name "Net-(C64-Pad1)") (class "Default")
      (node (ref "C64") (pin "1") (pinfunction "1_1") (pintype "passive"))
      (node (ref "T2") (pin "3") (pinfunction "3_3") (pintype "passive"))
    )
    (net (code "31") (name "Net-(D10-PadA)") (class "Default")
      (node (ref "D10") (pin "A") (pinfunction "A_A") (pintype "passive"))
      (node (ref "R15") (pin "1") (pinfunction "1_1") (pintype "passive"))
    )
    (net (code "32") (name "Net-(D11-PadA)") (class "Default")
      (node (ref "D11") (pin "A") (pinfunction "A_A") (pintype "passive"))
      (node (ref "R16") (pin "1") (pinfunction "1_1") (pintype "passive"))
    )
    (net (code "33") (name "Net-(D12-PadA)") (class "Default")
      (node (ref "D12") (pin "A") (pinfunction "A_A") (pintype "passive"))
      (node (ref "R18") (pin "1") (pinfunction "1_1") (pintype "passive"))
    )
    (net (code "34") (name "Net-(D13-PadA)") (class "Default")
      (node (ref "D13") (pin "A") (pinfunction "A_A") (pintype "passive"))
      (node (ref "R20") (pin "1") (pinfunction "1_1") (pintype "passive"))
    )
    (net (code "35") (name "Net-(J8-Pad1)") (class "Default")
      (node (ref "J8") (pin "1") (pinfunction "1_1") (pintype "passive"))
      (node (ref "T2") (pin "1") (pinfunction "1_1") (pintype "passive"))
    )
    (net (code "36") (name "Net-(U4-CLKTUNE)") (class "Default")
      (node (ref "C47") (pin "1") (pinfunction "1_1") (pintype "passive"))
      (node (ref "R17") (pin "1") (pinfunction "1_1") (pintype "passive"))
      (node (ref "U4") (pin "8") (pinfunction "CLKTUNE_8") (pintype "passive"))
    )
    (net (code "37") (name "Net-(U4-VCOTUNE)") (class "Default")
      (node (ref "C54") (pin "1") (pinfunction "1_1") (pintype "passive"))
      (node (ref "R19") (pin "2") (pinfunction "2_2") (pintype "passive"))
      (node (ref "U4") (pin "12") (pinfunction "VCOTUNE_12") (pintype "passive"))
    )
    (net (code "38") (name "Net-(U4-VDDDIG)") (class "Default")
      (node (ref "C37") (pin "1") (pinfunction "1_1") (pintype "passive"))
      (node (ref "C44") (pin "1") (pinfunction "1_1") (pintype "passive"))
      (node (ref "U4") (pin "20") (pinfunction "VDDREG_20") (pintype "passive"))
      (node (ref "U4") (pin "44") (pinfunction "VDDDIG_44") (pintype "passive"))
    )
    (net (code "39") (name "Net-(U4-VDDIF)") (class "Default")
      (node (ref "C58") (pin "1") (pinfunction "1_1") (pintype "passive"))
      (node (ref "U4") (pin "7") (pinfunction "VDDIF_7") (pintype "passive"))
    )
    (net (code "40") (name "Net-(U4-VDDIOA)") (class "Default")
      (node (ref "C36") (pin "1") (pinfunction "1_1") (pintype "passive"))
      (node (ref "U4") (pin "28") (pinfunction "VDDIOA_28") (pintype "passive"))
    )
    (net (code "41") (name "Net-(U4-VDDMS)") (class "Default")
      (node (ref "C57") (pin "1") (pinfunction "1_1") (pintype "passive"))
      (node (ref "U4") (pin "6") (pinfunction "VDDMS_6") (pintype "passive"))
    )
    (net (code "42") (name "Net-(U4-VDDPA1)") (class "Default")
      (node (ref "C40") (pin "2") (pinfunction "2_2") (pintype "passive"))
      (node (ref "C41") (pin "2") (pinfunction "2_2") (pintype "passive"))
      (node (ref "C42") (pin "2") (pinfunction "2_2") (pintype "passive"))
      (node (ref "C43") (pin "2") (pinfunction "2_2") (pintype "passive"))
      (node (ref "L3") (pin "2") (pinfunction "2_2") (pintype "passive"))
      (node (ref "U4") (pin "18") (pinfunction "VDDPA1_18") (pintype "passive"))
    )
    (net (code "43") (name "Net-(U4-VDDPA2)") (class "Default")
      (node (ref "C48") (pin "2") (pinfunction "2_2") (pintype "passive"))
      (node (ref "C49") (pin "2") (pinfunction "2_2") (pintype "passive"))
      (node (ref "C50") (pin "2") (pinfunction "2_2") (pintype "passive"))
      (node (ref "C51") (pin "2") (pinfunction "2_2") (pintype "passive"))
      (node (ref "L4") (pin "2") (pinfunction "2_2") (pintype "passive"))
      (node (ref "U4") (pin "19") (pinfunction "VDDPA2_19") (pintype "passive"))
    )
    (net (code "44") (name "Net-(U4-VDDSYN)") (class "Default")
      (node (ref "C60") (pin "1") (pinfunction "1_1") (pintype "passive"))
      (node (ref "U4") (pin "10") (pinfunction "VDDSYN_10") (pintype "passive"))
    )
    (net (code "45") (name "Net-(U4-VREF)") (class "Default")
      (node (ref "R21") (pin "2") (pinfunction "2_2") (pintype "passive"))
      (node (ref "U4") (pin "5") (pinfunction "VREF_5") (pintype "passive"))
    )
    (net (code "46") (name "Net-(U4-XTAL2)") (class "Default")
      (node (ref "C62") (pin "2") (pinfunction "2_2") (pintype "passive"))
      (node (ref "U4") (pin "4") (pinfunction "XTAL2_4") (pintype "passive"))
    )
    (net (code "47") (name "unconnected-(T2-NC-Pad6)") (class "Default")
      (node (ref "T2") (pin "6") (pinfunction "NC_6") (pintype "passive+no_connect"))
    )
    (net (code "48") (name "unconnected-(U4-NC-Pad1)") (class "Default")
      (node (ref "U4") (pin "1") (pinfunction "NC_1") (pintype "passive+no_connect"))
    )
    (net (code "49") (name "unconnected-(U4-NC-Pad2)") (class "Default")
      (node (ref "U4") (pin "2") (pinfunction "NC_2") (pintype "passive+no_connect"))
    )
    (net (code "50") (name "unconnected-(U4-NC-Pad13)") (class "Default")
      (node (ref "U4") (pin "13") (pinfunction "NC_13") (pintype "passive+no_connect"))
    )
    (net (code "51") (name "unconnected-(U4-NC-Pad14)") (class "Default")
      (node (ref "U4") (pin "14") (pinfunction "NC_14") (pintype "passive+no_connect"))
    )
  )
)
